# CapstoneREV_10-5-25_2.net
KiCad netlist of a schematic drawn in EAGLE
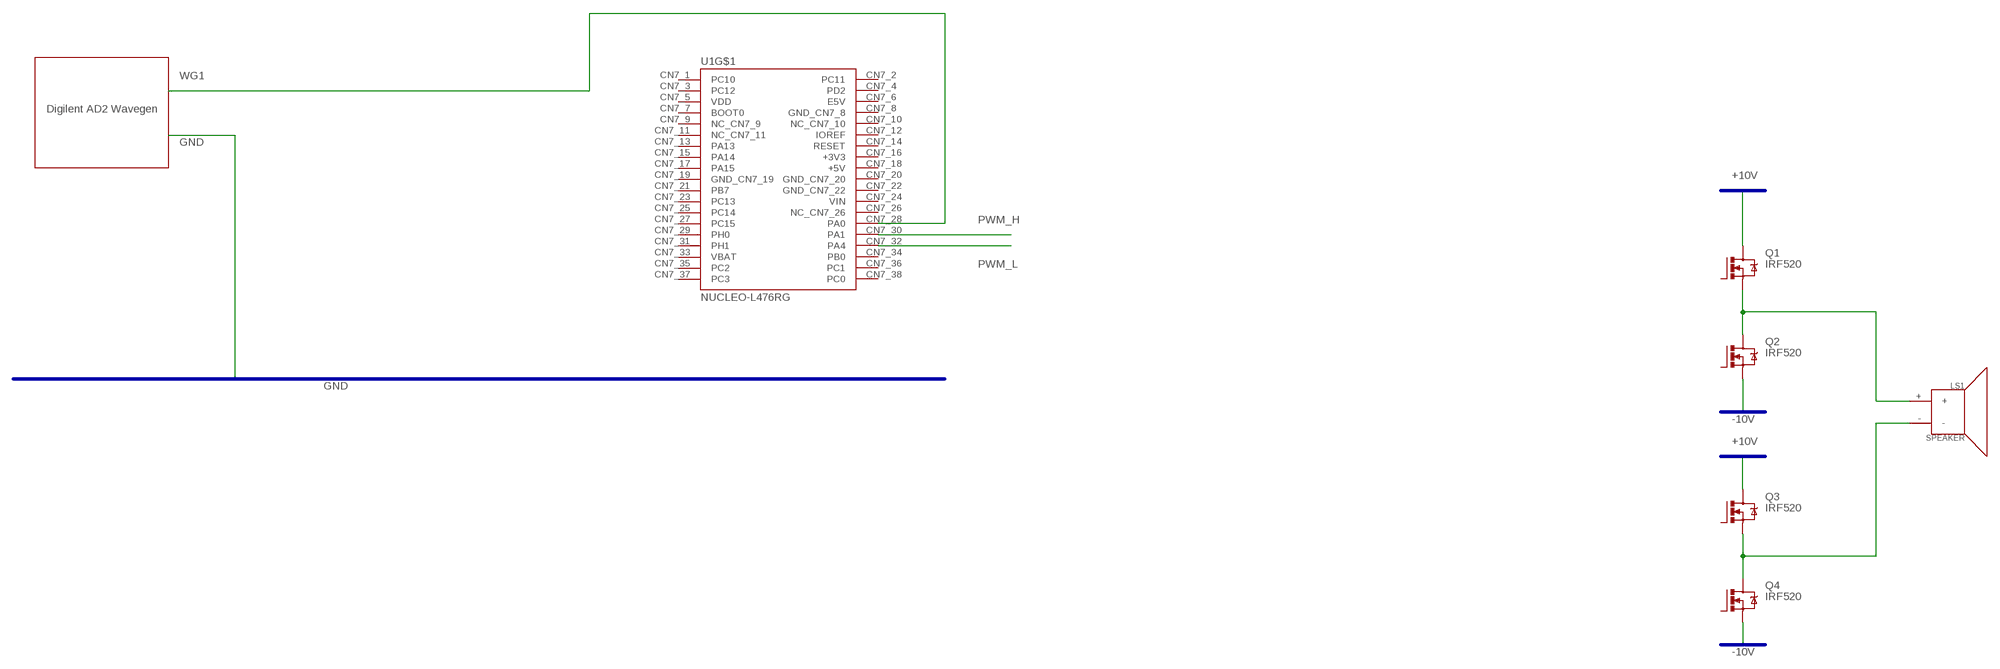
[diagram p0: schematic, sheet 1]

(export (version "E")
  (design (tool "Eeschema 10.0.6"))
  (components
    (comp (ref "LS1")
      (value "SPEAKER")
      (footprint "eagle-import:PCB_MOUNT_SPEAKER")
      (libsource (lib "eagle-import") (part "SPEAKER"))
    )
    (comp (ref "Q1")
      (value "IRF520")
      (footprint "eagle-import:TO220BV")
      (libsource (lib "eagle-import") (part "IRF520"))
    )
    (comp (ref "Q2")
      (value "IRF520")
      (footprint "eagle-import:TO220BV")
      (libsource (lib "eagle-import") (part "IRF520"))
    )
    (comp (ref "Q3")
      (value "IRF520")
      (footprint "eagle-import:TO220BV")
      (libsource (lib "eagle-import") (part "IRF520"))
    )
    (comp (ref "Q4")
      (value "IRF520")
      (footprint "eagle-import:TO220BV")
      (libsource (lib "eagle-import") (part "IRF520"))
    )
    (comp (ref "U1")
      (value "NUCLEO-L476RG")
      (footprint "eagle-import:MODULE_NUCLEO-L476RG")
      (fields (field (name "MANUFACTURER") "STmicroelectronics"))
      (libsource (lib "eagle-import") (part "NUCLEO-L476RG"))
    )
  )
  (nets
    (net (code "2") (name "/+3V3") (class "Default")
      (node (ref "U1") (pin "CN7_16") (pinfunction "+3V3_CN7_16") (pintype "power_in"))
    )
    (net (code "3") (name "/+5V") (class "Default")
      (node (ref "U1") (pin "CN7_18") (pinfunction "+5V_CN7_18") (pintype "power_in"))
    )
    (net (code "5") (name "/-10V") (class "Default")
      (node (ref "Q2") (pin "S") (pinfunction "S_S") (pintype "passive"))
    )
    (net (code "7") (name "/E5V") (class "Default")
      (node (ref "U1") (pin "CN7_6") (pinfunction "E5V_CN7_6") (pintype "power_in"))
    )
    (net (code "8") (name "/GND_CN7_8") (class "Default")
      (node (ref "U1") (pin "CN7_8") (pinfunction "GND_CN7_8_CN7_8") (pintype "power_in"))
    )
    (net (code "9") (name "/GND_CN7_19") (class "Default")
      (node (ref "U1") (pin "CN7_19") (pinfunction "GND_CN7_19_CN7_19") (pintype "power_in"))
    )
    (net (code "10") (name "/GND_CN7_20") (class "Default")
      (node (ref "U1") (pin "CN7_20") (pinfunction "GND_CN7_20_CN7_20") (pintype "power_in"))
    )
    (net (code "11") (name "/GND_CN7_22") (class "Default")
      (node (ref "U1") (pin "CN7_22") (pinfunction "GND_CN7_22_CN7_22") (pintype "power_in"))
    )
    (net (code "12") (name "/PWM_H") (class "Default")
      (node (ref "U1") (pin "CN7_30") (pinfunction "PA1_CN7_30") (pintype "bidirectional"))
    )
    (net (code "13") (name "/PWM_L") (class "Default")
      (node (ref "U1") (pin "CN7_32") (pinfunction "PA4_CN7_32") (pintype "bidirectional"))
    )
    (net (code "14") (name "/VBAT") (class "Default")
      (node (ref "U1") (pin "CN7_33") (pinfunction "VBAT_CN7_33") (pintype "power_in"))
    )
    (net (code "15") (name "/VDD") (class "Default")
      (node (ref "U1") (pin "CN7_5") (pinfunction "VDD_CN7_5") (pintype "power_in"))
    )
    (net (code "19") (name "/VIN") (class "Default")
      (node (ref "U1") (pin "CN7_24") (pinfunction "VIN_CN7_24") (pintype "power_in"))
    )
    (net (code "20") (name "Net-(LS1-Pad+)") (class "Default")
      (node (ref "LS1") (pin "+") (pinfunction "+_+") (pintype "bidirectional"))
      (node (ref "Q1") (pin "S") (pinfunction "S_S") (pintype "passive"))
      (node (ref "Q2") (pin "D") (pinfunction "D_D") (pintype "passive"))
    )
    (net (code "21") (name "Net-(LS1-Pad-)") (class "Default")
      (node (ref "LS1") (pin "-") (pinfunction "-_-") (pintype "bidirectional"))
      (node (ref "Q3") (pin "S") (pinfunction "S_S") (pintype "passive"))
      (node (ref "Q4") (pin "D") (pinfunction "D_D") (pintype "passive"))
    )
    (net (code "22") (name "unconnected-(Q1-PadD)") (class "Default")
      (node (ref "Q1") (pin "D") (pinfunction "D_D") (pintype "passive"))
    )
    (net (code "23") (name "unconnected-(Q1-PadG)") (class "Default")
      (node (ref "Q1") (pin "G") (pinfunction "G_G") (pintype "passive"))
    )
    (net (code "24") (name "unconnected-(Q2-PadG)") (class "Default")
      (node (ref "Q2") (pin "G") (pinfunction "G_G") (pintype "passive"))
    )
    (net (code "25") (name "unconnected-(Q3-PadD)") (class "Default")
      (node (ref "Q3") (pin "D") (pinfunction "D_D") (pintype "passive"))
    )
    (net (code "26") (name "unconnected-(Q3-PadG)") (class "Default")
      (node (ref "Q3") (pin "G") (pinfunction "G_G") (pintype "passive"))
    )
    (net (code "27") (name "unconnected-(Q4-PadG)") (class "Default")
      (node (ref "Q4") (pin "G") (pinfunction "G_G") (pintype "passive"))
    )
    (net (code "28") (name "unconnected-(Q4-PadS)") (class "Default")
      (node (ref "Q4") (pin "S") (pinfunction "S_S") (pintype "passive"))
    )
    (net (code "29") (name "unconnected-(U1A-BOOT0-PadCN7_7)") (class "Default")
      (node (ref "U1") (pin "CN7_7") (pinfunction "BOOT0_CN7_7") (pintype "input"))
    )
    (net (code "30") (name "unconnected-(U1A-IOREF-PadCN7_12)") (class "Default")
      (node (ref "U1") (pin "CN7_12") (pinfunction "IOREF_CN7_12") (pintype "input"))
    )
    (net (code "31") (name "unconnected-(U1A-NC_CN7_9-PadCN7_9)") (class "Default")
      (node (ref "U1") (pin "CN7_9") (pinfunction "NC_CN7_9_CN7_9") (pintype "no_connect"))
    )
    (net (code "32") (name "unconnected-(U1A-NC_CN7_10-PadCN7_10)") (class "Default")
      (node (ref "U1") (pin "CN7_10") (pinfunction "NC_CN7_10_CN7_10") (pintype "no_connect"))
    )
    (net (code "33") (name "unconnected-(U1A-NC_CN7_11-PadCN7_11)") (class "Default")
      (node (ref "U1") (pin "CN7_11") (pinfunction "NC_CN7_11_CN7_11") (pintype "no_connect"))
    )
    (net (code "34") (name "unconnected-(U1A-NC_CN7_26-PadCN7_26)") (class "Default")
      (node (ref "U1") (pin "CN7_26") (pinfunction "NC_CN7_26_CN7_26") (pintype "no_connect"))
    )
    (net (code "35") (name "unconnected-(U1A-PA0-PadCN7_28)") (class "Default")
      (node (ref "U1") (pin "CN7_28") (pinfunction "PA0_CN7_28") (pintype "bidirectional"))
    )
    (net (code "36") (name "unconnected-(U1A-PA13-PadCN7_13)") (class "Default")
      (node (ref "U1") (pin "CN7_13") (pinfunction "PA13_CN7_13") (pintype "bidirectional"))
    )
    (net (code "37") (name "unconnected-(U1A-PA14-PadCN7_15)") (class "Default")
      (node (ref "U1") (pin "CN7_15") (pinfunction "PA14_CN7_15") (pintype "bidirectional"))
    )
    (net (code "38") (name "unconnected-(U1A-PA15-PadCN7_17)") (class "Default")
      (node (ref "U1") (pin "CN7_17") (pinfunction "PA15_CN7_17") (pintype "bidirectional"))
    )
    (net (code "39") (name "unconnected-(U1A-PB0-PadCN7_34)") (class "Default")
      (node (ref "U1") (pin "CN7_34") (pinfunction "PB0_CN7_34") (pintype "bidirectional"))
    )
    (net (code "40") (name "unconnected-(U1A-PB7-PadCN7_21)") (class "Default")
      (node (ref "U1") (pin "CN7_21") (pinfunction "PB7_CN7_21") (pintype "bidirectional"))
    )
    (net (code "41") (name "unconnected-(U1A-PC0-PadCN7_38)") (class "Default")
      (node (ref "U1") (pin "CN7_38") (pinfunction "PC0_CN7_38") (pintype "bidirectional"))
    )
    (net (code "42") (name "unconnected-(U1A-PC1-PadCN7_36)") (class "Default")
      (node (ref "U1") (pin "CN7_36") (pinfunction "PC1_CN7_36") (pintype "bidirectional"))
    )
    (net (code "43") (name "unconnected-(U1A-PC2-PadCN7_35)") (class "Default")
      (node (ref "U1") (pin "CN7_35") (pinfunction "PC2_CN7_35") (pintype "bidirectional"))
    )
    (net (code "44") (name "unconnected-(U1A-PC3-PadCN7_37)") (class "Default")
      (node (ref "U1") (pin "CN7_37") (pinfunction "PC3_CN7_37") (pintype "bidirectional"))
    )
    (net (code "45") (name "unconnected-(U1A-PC10-PadCN7_1)") (class "Default")
      (node (ref "U1") (pin "CN7_1") (pinfunction "PC10_CN7_1") (pintype "bidirectional"))
    )
    (net (code "46") (name "unconnected-(U1A-PC11-PadCN7_2)") (class "Default")
      (node (ref "U1") (pin "CN7_2") (pinfunction "PC11_CN7_2") (pintype "bidirectional"))
    )
    (net (code "47") (name "unconnected-(U1A-PC12-PadCN7_3)") (class "Default")
      (node (ref "U1") (pin "CN7_3") (pinfunction "PC12_CN7_3") (pintype "bidirectional"))
    )
    (net (code "48") (name "unconnected-(U1A-PC13-PadCN7_23)") (class "Default")
      (node (ref "U1") (pin "CN7_23") (pinfunction "PC13_CN7_23") (pintype "bidirectional"))
    )
    (net (code "49") (name "unconnected-(U1A-PC14-PadCN7_25)") (class "Default")
      (node (ref "U1") (pin "CN7_25") (pinfunction "PC14_CN7_25") (pintype "bidirectional"))
    )
    (net (code "50") (name "unconnected-(U1A-PC15-PadCN7_27)") (class "Default")
      (node (ref "U1") (pin "CN7_27") (pinfunction "PC15_CN7_27") (pintype "bidirectional"))
    )
    (net (code "51") (name "unconnected-(U1A-PD2-PadCN7_4)") (class "Default")
      (node (ref "U1") (pin "CN7_4") (pinfunction "PD2_CN7_4") (pintype "bidirectional"))
    )
    (net (code "52") (name "unconnected-(U1A-PH0-PadCN7_29)") (class "Default")
      (node (ref "U1") (pin "CN7_29") (pinfunction "PH0_CN7_29") (pintype "bidirectional"))
    )
    (net (code "53") (name "unconnected-(U1A-PH1-PadCN7_31)") (class "Default")
      (node (ref "U1") (pin "CN7_31") (pinfunction "PH1_CN7_31") (pintype "bidirectional"))
    )
    (net (code "54") (name "unconnected-(U1A-RESET-PadCN7_14)") (class "Default")
      (node (ref "U1") (pin "CN7_14") (pinfunction "RESET_CN7_14") (pintype "input"))
    )
  )
)
